# GD_AirIrDA_IrDA.net
KiCad netlist of a schematic drawn in Altium Designer
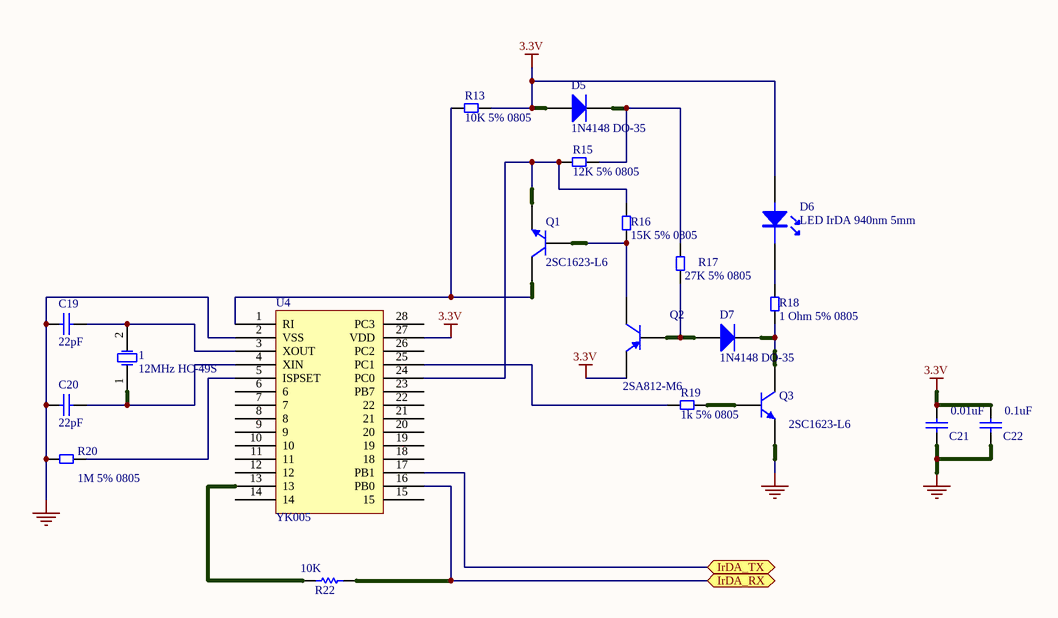
[diagram p0: GD_AirIrDA_IrDA.SchDoc]

(export (version "E")
  (design (tool "Eeschema 10.0.6"))
  (components
    (comp (ref "1")
      (value "12MHz HC-49S")
      (footprint "XTAL_US")
      (fields (field (name "PUBLISHER") "Altium Limited"))
      (libsource (lib "战舰STM32开发板底板封装库") (part "XTAL"))
    )
    (comp (ref "C19")
      (value "22pF")
      (footprint "CAPC0805(2012)75_M")
      (description "CAP 22pF 50V ±1% 0805 (2012 Metric) Thickness 0.75mm SMD")
      (fields (field (name "TOLERANCE") "±1%") (field (name "Comment") "CAP 22pF 5% 50V 0805"))
      (libsource (lib "Altium Content Vault") (part "CMP-1036-01234-1"))
    )
    (comp (ref "C20")
      (value "22pF")
      (footprint "CAPC0805(2012)75_M")
      (description "CAP 22pF 50V ±1% 0805 (2012 Metric) Thickness 0.75mm SMD")
      (fields (field (name "TOLERANCE") "±1%") (field (name "Comment") "CAP 22pF 5% 50V 0805"))
      (libsource (lib "Altium Content Vault") (part "CMP-1036-01234-1"))
    )
    (comp (ref "C21")
      (value "0.01uF")
      (footprint "CAPC0805(2012)100_N")
      (description "CAP 0.1uF 50V ±20% 0805 (2012 Metric) Thickness 1mm SMD")
      (fields (field (name "TOLERANCE") "20%") (field (name "Comment") "CAP 0.01uF 20% 50V 0805"))
      (libsource (lib "Altium Content Vault") (part "CMP-1036-00070-1"))
    )
    (comp (ref "C22")
      (value "0.1uF")
      (footprint "CAPC0805(2012)100_N")
      (description "CAP 0.1uF 50V ±20% 0805 (2012 Metric) Thickness 1mm SMD")
      (fields (field (name "TOLERANCE") "20%") (field (name "Comment") "CAP 0.1uF 20% 50V 0805"))
      (libsource (lib "Altium Content Vault") (part "CMP-1036-00070-1"))
    )
    (comp (ref "D5")
      (value "1N4148 DO-35")
      (footprint "NXP-SOD27-2_V")
      (description "High-speed Diode, 100 V, 450 mA, 2-Pin SOD27, RoHS")
      (fields (field (name "PARTNUMBER") "1N4148") (field (name "MANUFACTURER") "NXP Semiconductors"))
      (libsource (lib "Altium Content Vault") (part "NXP-A1K2-2"))
    )
    (comp (ref "D6") (value "LED IrDA 940nm 5mm") (footprint "LED-5.0") (libsource (lib "*") (part "LED")))
    (comp (ref "D7")
      (value "1N4148 DO-35")
      (footprint "NXP-SOD27-2_V")
      (description "High-speed Diode, 100 V, 450 mA, 2-Pin SOD27, RoHS")
      (fields (field (name "PARTNUMBER") "1N4148") (field (name "MANUFACTURER") "NXP Semiconductors"))
      (libsource (lib "Altium Content Vault") (part "NXP-A1K2-2"))
    )
    (comp (ref "Q1")
      (value "2SC1623-L6")
      (footprint "SOT-23B_N")
      (description "NPN Bipolar Transistor")
      (fields (field (name "PUBLISHER") "Altium Limited"))
      (libsource (lib "Miscellaneous Devices") (part "QNPN"))
    )
    (comp (ref "Q2")
      (value "2SA812-M6")
      (footprint "SOT-23B_N")
      (description "PNP Bipolar Transistor")
      (fields (field (name "PUBLISHER") "Altium Limited"))
      (libsource (lib "Miscellaneous Devices") (part "PNP"))
    )
    (comp (ref "Q3")
      (value "2SC1623-L6")
      (footprint "SOT-23B_N")
      (description "NPN Bipolar Transistor")
      (fields (field (name "PUBLISHER") "Altium Limited"))
      (libsource (lib "Miscellaneous Devices") (part "QNPN"))
    )
    (comp (ref "R13") (value "10K 5% 0805") (footprint "R0805") (libsource (lib "*") (part "RES2")))
    (comp (ref "R15") (value "12K 5% 0805") (footprint "R0805") (libsource (lib "*") (part "RES2")))
    (comp (ref "R16") (value "15K 5% 0805") (footprint "R0805") (libsource (lib "*") (part "RES2")))
    (comp (ref "R17") (value "27K 5% 0805") (footprint "R0805") (libsource (lib "*") (part "RES2")))
    (comp (ref "R18") (value "1 Ohm 5% 0805") (footprint "R0805") (libsource (lib "*") (part "RES2")))
    (comp (ref "R19") (value "1k 5% 0805") (footprint "R0805") (libsource (lib "*") (part "RES2")))
    (comp (ref "R20") (value "1M 5% 0805") (footprint "R0805") (libsource (lib "*") (part "RES2")))
    (comp (ref "R22")
      (value "10K")
      (footprint "RESC0805(2012)_L")
      (description "10K 0.125W 5% 0805 (2012 Metric)  SMD")
      (fields (field (name "POWER") "0.125 W") (field (name "TOLERANCE") "5 %"))
      (libsource (lib "Altium Content Vault") (part "CMP-1013-00098-1"))
    )
    (comp (ref "U4")
      (value "YK005")
      (footprint "IR-IC")
      (description "福建易控电子")
      (libsource (lib "*") (part "KT-003"))
    )
  )
  (nets
    (net (code "1") (name "/IrDA_RX") (class "Default")
      (node (ref "R22") (pin "2") (pinfunction "2_2") (pintype "passive"))
      (node (ref "U4") (pin "16") (pinfunction "PB0_16") (pintype "passive"))
    )
    (net (code "2") (name "/IrDA_TX") (class "Default")
      (node (ref "U4") (pin "17") (pinfunction "PB1_17") (pintype "passive"))
    )
    (net (code "3") (name "3.3V") (class "Default")
      (node (ref "C21") (pin "2") (pinfunction "2_2") (pintype "passive"))
      (node (ref "C22") (pin "2") (pinfunction "2_2") (pintype "passive"))
      (node (ref "D5") (pin "1") (pinfunction "A_1") (pintype "passive"))
      (node (ref "D6") (pin "1") (pinfunction "1_1") (pintype "passive"))
      (node (ref "Q2") (pin "3") (pinfunction "E_3") (pintype "passive"))
      (node (ref "R13") (pin "2") (pinfunction "2_2") (pintype "passive"))
      (node (ref "U4") (pin "27") (pinfunction "VDD_27") (pintype "passive"))
    )
    (net (code "4") (name "GND") (class "Default")
      (node (ref "C19") (pin "2") (pinfunction "2_2") (pintype "passive"))
      (node (ref "C20") (pin "2") (pinfunction "2_2") (pintype "passive"))
      (node (ref "C21") (pin "1") (pinfunction "1_1") (pintype "passive"))
      (node (ref "C22") (pin "1") (pinfunction "1_1") (pintype "passive"))
      (node (ref "Q3") (pin "3") (pinfunction "E_3") (pintype "passive"))
      (node (ref "R20") (pin "1") (pinfunction "1_1") (pintype "passive"))
      (node (ref "U4") (pin "2") (pinfunction "VSS_2") (pintype "passive"))
    )
    (net (code "5") (name "Net-(1-OSC1)") (class "Default")
      (node (ref "1") (pin "1") (pinfunction "OSC1_1") (pintype "passive"))
      (node (ref "C20") (pin "1") (pinfunction "1_1") (pintype "passive"))
      (node (ref "U4") (pin "4") (pinfunction "XIN_4") (pintype "passive"))
    )
    (net (code "6") (name "Net-(1-OSC2)") (class "Default")
      (node (ref "1") (pin "2") (pinfunction "OSC2_2") (pintype "passive"))
      (node (ref "C19") (pin "1") (pinfunction "1_1") (pintype "passive"))
      (node (ref "U4") (pin "3") (pinfunction "XOUT_3") (pintype "passive"))
    )
    (net (code "7") (name "Net-(D5-K)") (class "Default")
      (node (ref "D5") (pin "2") (pinfunction "K_2") (pintype "passive"))
      (node (ref "R15") (pin "2") (pinfunction "2_2") (pintype "passive"))
      (node (ref "R17") (pin "2") (pinfunction "2_2") (pintype "passive"))
    )
    (net (code "8") (name "Net-(D6-Pad2)") (class "Default")
      (node (ref "D6") (pin "2") (pinfunction "2_2") (pintype "passive"))
      (node (ref "R18") (pin "2") (pinfunction "2_2") (pintype "passive"))
    )
    (net (code "9") (name "Net-(D7-A)") (class "Default")
      (node (ref "D7") (pin "1") (pinfunction "A_1") (pintype "passive"))
      (node (ref "Q2") (pin "2") (pinfunction "B_2") (pintype "passive"))
      (node (ref "R17") (pin "1") (pinfunction "1_1") (pintype "passive"))
    )
    (net (code "10") (name "Net-(D7-K)") (class "Default")
      (node (ref "D7") (pin "2") (pinfunction "K_2") (pintype "passive"))
      (node (ref "Q3") (pin "1") (pinfunction "C_1") (pintype "passive"))
      (node (ref "R18") (pin "1") (pinfunction "1_1") (pintype "passive"))
    )
    (net (code "11") (name "Net-(Q1-B)") (class "Default")
      (node (ref "Q1") (pin "2") (pinfunction "B_2") (pintype "passive"))
      (node (ref "Q2") (pin "1") (pinfunction "C_1") (pintype "passive"))
      (node (ref "R16") (pin "2") (pinfunction "2_2") (pintype "passive"))
    )
    (net (code "12") (name "Net-(Q1-C)") (class "Default")
      (node (ref "Q1") (pin "1") (pinfunction "C_1") (pintype "passive"))
      (node (ref "R13") (pin "1") (pinfunction "1_1") (pintype "passive"))
      (node (ref "U4") (pin "1") (pinfunction "RI_1") (pintype "passive"))
    )
    (net (code "13") (name "Net-(Q1-E)") (class "Default")
      (node (ref "Q1") (pin "3") (pinfunction "E_3") (pintype "passive"))
      (node (ref "R15") (pin "1") (pinfunction "1_1") (pintype "passive"))
      (node (ref "R16") (pin "1") (pinfunction "1_1") (pintype "passive"))
      (node (ref "U4") (pin "24") (pinfunction "PC0_24") (pintype "passive"))
    )
    (net (code "14") (name "Net-(Q3-B)") (class "Default")
      (node (ref "Q3") (pin "2") (pinfunction "B_2") (pintype "passive"))
      (node (ref "R19") (pin "2") (pinfunction "2_2") (pintype "passive"))
    )
    (net (code "15") (name "Net-(R22-Pad1)") (class "Default")
      (node (ref "R22") (pin "1") (pinfunction "1_1") (pintype "passive"))
      (node (ref "U4") (pin "13") (pinfunction "13_13") (pintype "passive"))
    )
    (net (code "16") (name "Net-(U4-ISPSET)") (class "Default")
      (node (ref "R20") (pin "2") (pinfunction "2_2") (pintype "passive"))
      (node (ref "U4") (pin "5") (pinfunction "ISPSET_5") (pintype "passive"))
    )
    (net (code "17") (name "Net-(U4-PC1)") (class "Default")
      (node (ref "R19") (pin "1") (pinfunction "1_1") (pintype "passive"))
      (node (ref "U4") (pin "25") (pinfunction "PC1_25") (pintype "passive"))
    )
    (net (code "18") (name "unconnected-(U4-PB7-Pad23)") (class "Default")
      (node (ref "U4") (pin "23") (pinfunction "PB7_23") (pintype "passive"))
    )
    (net (code "19") (name "unconnected-(U4-PC2-Pad26)") (class "Default")
      (node (ref "U4") (pin "26") (pinfunction "PC2_26") (pintype "passive"))
    )
    (net (code "20") (name "unconnected-(U4-PC3-Pad28)") (class "Default")
      (node (ref "U4") (pin "28") (pinfunction "PC3_28") (pintype "passive"))
    )
    (net (code "21") (name "unconnected-(U4-Pad6)") (class "Default")
      (node (ref "U4") (pin "6") (pinfunction "6_6") (pintype "passive"))
    )
    (net (code "22") (name "unconnected-(U4-Pad7)") (class "Default")
      (node (ref "U4") (pin "7") (pinfunction "7_7") (pintype "passive"))
    )
    (net (code "23") (name "unconnected-(U4-Pad8)") (class "Default")
      (node (ref "U4") (pin "8") (pinfunction "8_8") (pintype "passive"))
    )
    (net (code "24") (name "unconnected-(U4-Pad9)") (class "Default")
      (node (ref "U4") (pin "9") (pinfunction "9_9") (pintype "passive"))
    )
    (net (code "25") (name "unconnected-(U4-Pad10)") (class "Default")
      (node (ref "U4") (pin "10") (pinfunction "10_10") (pintype "passive"))
    )
    (net (code "26") (name "unconnected-(U4-Pad11)") (class "Default")
      (node (ref "U4") (pin "11") (pinfunction "11_11") (pintype "passive"))
    )
    (net (code "27") (name "unconnected-(U4-Pad12)") (class "Default")
      (node (ref "U4") (pin "12") (pinfunction "12_12") (pintype "passive"))
    )
    (net (code "28") (name "unconnected-(U4-Pad14)") (class "Default")
      (node (ref "U4") (pin "14") (pinfunction "14_14") (pintype "passive"))
    )
    (net (code "29") (name "unconnected-(U4-Pad15)") (class "Default")
      (node (ref "U4") (pin "15") (pinfunction "15_15") (pintype "passive"))
    )
    (net (code "30") (name "unconnected-(U4-Pad18)") (class "Default")
      (node (ref "U4") (pin "18") (pinfunction "18_18") (pintype "passive"))
    )
    (net (code "31") (name "unconnected-(U4-Pad19)") (class "Default")
      (node (ref "U4") (pin "19") (pinfunction "19_19") (pintype "passive"))
    )
    (net (code "32") (name "unconnected-(U4-Pad20)") (class "Default")
      (node (ref "U4") (pin "20") (pinfunction "20_20") (pintype "passive"))
    )
    (net (code "33") (name "unconnected-(U4-Pad21)") (class "Default")
      (node (ref "U4") (pin "21") (pinfunction "21_21") (pintype "passive"))
    )
    (net (code "34") (name "unconnected-(U4-Pad22)") (class "Default")
      (node (ref "U4") (pin "22") (pinfunction "22_22") (pintype "passive"))
    )
  )
)
